# tally-controller-shield-smd.net
KiCad netlist of a schematic drawn in EAGLE
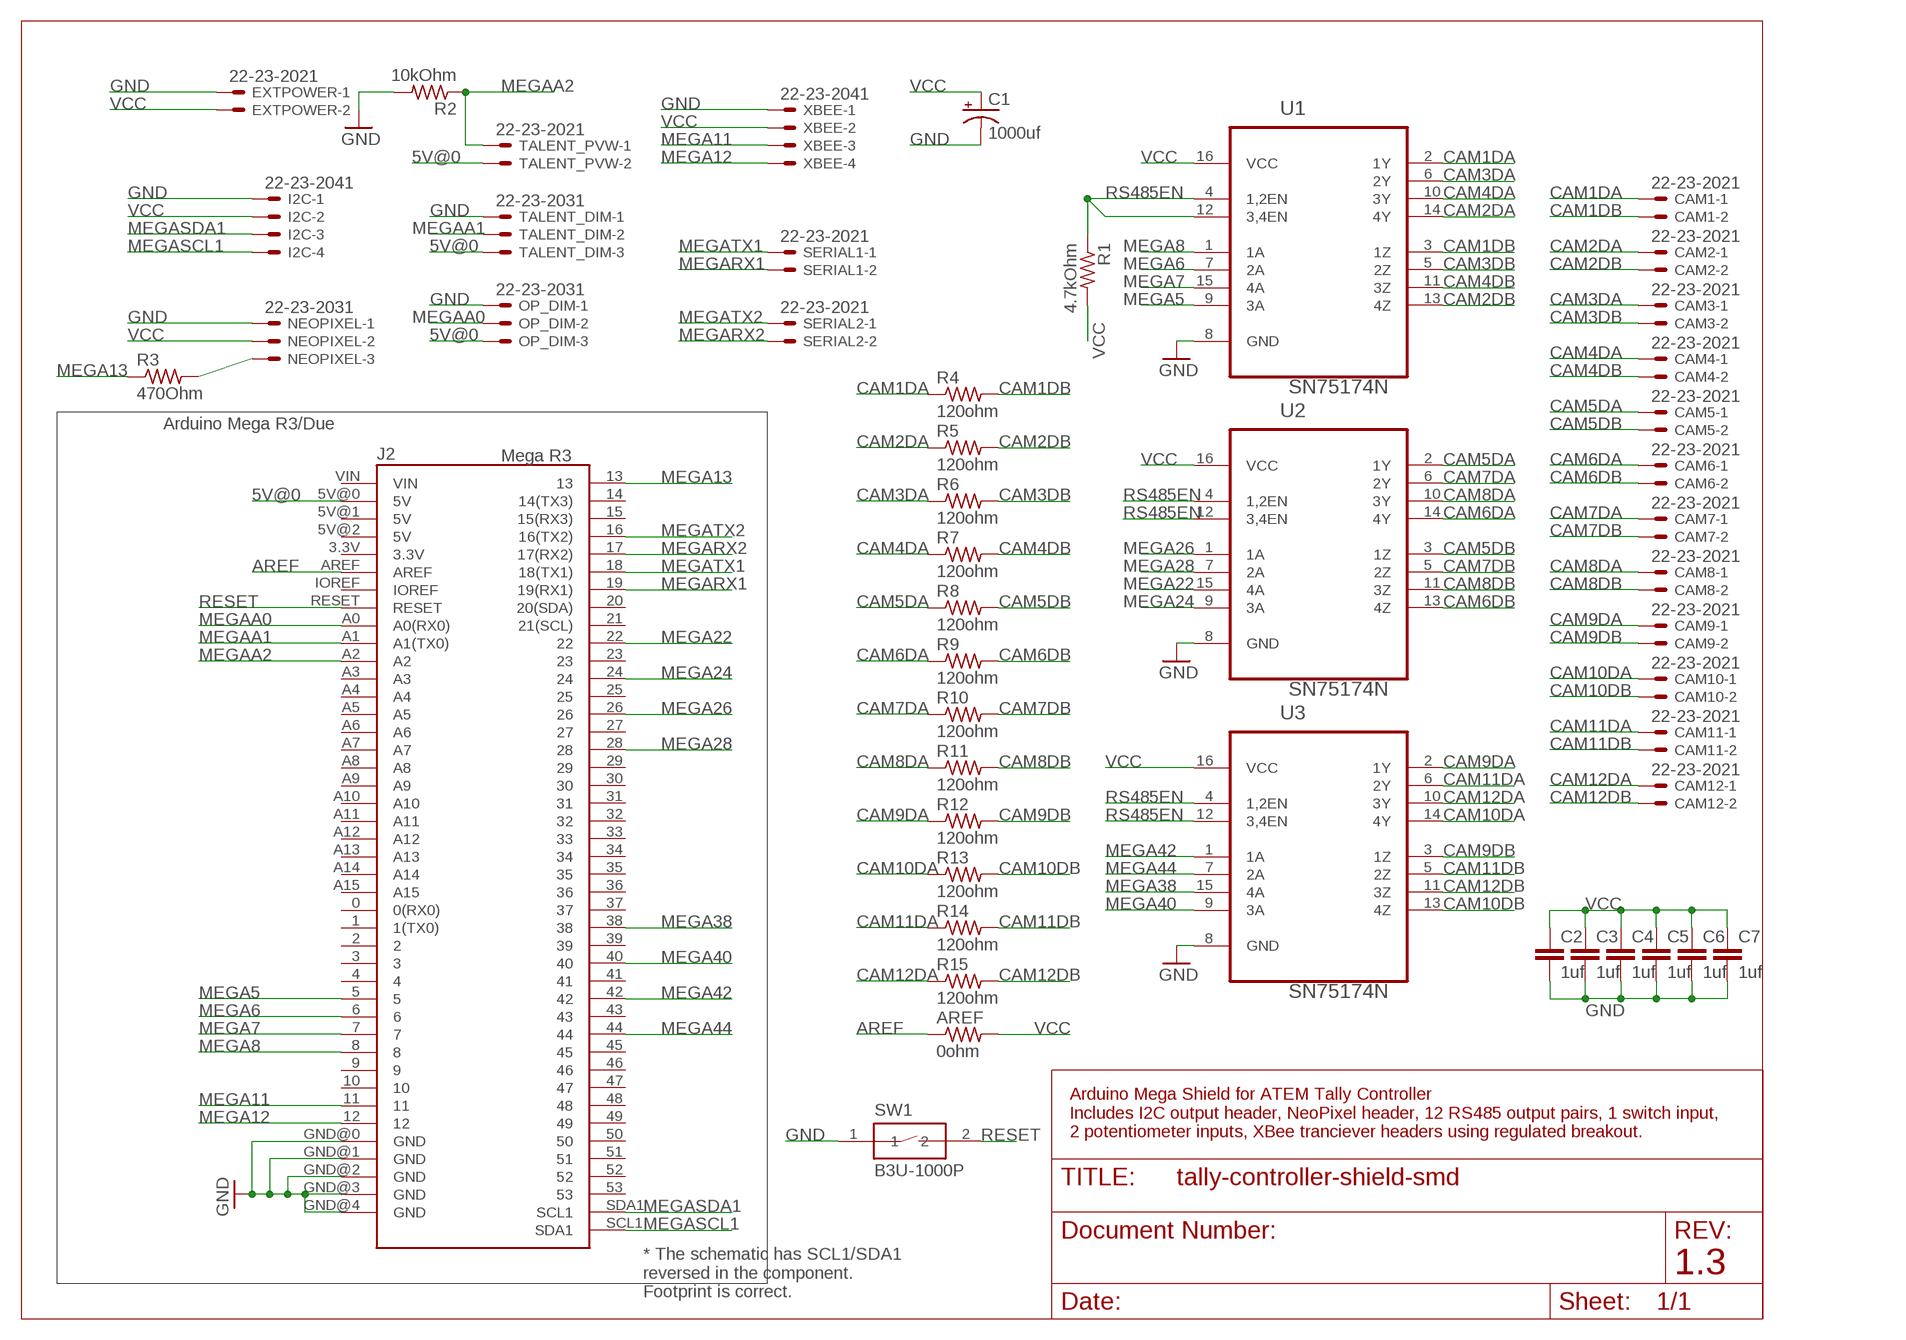
[diagram p0: schematic, sheet 1]

(export (version "E")
  (design (tool "Eeschema 10.0.6"))
  (components
    (comp (ref "AREF")
      (value "0ohm")
      (footprint "eagle-import:0204V")
      (libsource (lib "eagle-import") (part "R-US_0204/2V"))
    )
    (comp (ref "C1")
      (value "1000uf")
      (footprint "eagle-import:CPOL-RADIAL-5MM-10MM")
      (libsource (lib "eagle-import") (part "1000UF-RADIAL-5MM-25V-20%"))
    )
    (comp (ref "C2")
      (value "1uf")
      (footprint "eagle-import:RESC0805_N")
      (libsource (lib "eagle-import") (part "CAPACITOR_0805_N"))
    )
    (comp (ref "C3")
      (value "1uf")
      (footprint "eagle-import:RESC0805_N")
      (libsource (lib "eagle-import") (part "CAPACITOR_0805_N"))
    )
    (comp (ref "C4")
      (value "1uf")
      (footprint "eagle-import:RESC0805_N")
      (libsource (lib "eagle-import") (part "CAPACITOR_0805_N"))
    )
    (comp (ref "C5")
      (value "1uf")
      (footprint "eagle-import:RESC0805_N")
      (libsource (lib "eagle-import") (part "CAPACITOR_0805_N"))
    )
    (comp (ref "C6")
      (value "1uf")
      (footprint "eagle-import:RESC0805_N")
      (libsource (lib "eagle-import") (part "CAPACITOR_0805_N"))
    )
    (comp (ref "C7")
      (value "1uf")
      (footprint "eagle-import:RESC0805_N")
      (libsource (lib "eagle-import") (part "CAPACITOR_0805_N"))
    )
    (comp (ref "CAM1")
      (value "22-23-2021")
      (footprint "eagle-import:22-23-2021")
      (fields (field (name "MF") "MOLEX"))
      (libsource (lib "eagle-import") (part "22-23-2021"))
    )
    (comp (ref "CAM2")
      (value "22-23-2021")
      (footprint "eagle-import:22-23-2021")
      (fields (field (name "MF") "MOLEX"))
      (libsource (lib "eagle-import") (part "22-23-2021"))
    )
    (comp (ref "CAM3")
      (value "22-23-2021")
      (footprint "eagle-import:22-23-2021")
      (fields (field (name "MF") "MOLEX"))
      (libsource (lib "eagle-import") (part "22-23-2021"))
    )
    (comp (ref "CAM4")
      (value "22-23-2021")
      (footprint "eagle-import:22-23-2021")
      (fields (field (name "MF") "MOLEX"))
      (libsource (lib "eagle-import") (part "22-23-2021"))
    )
    (comp (ref "CAM5")
      (value "22-23-2021")
      (footprint "eagle-import:22-23-2021")
      (fields (field (name "MF") "MOLEX"))
      (libsource (lib "eagle-import") (part "22-23-2021"))
    )
    (comp (ref "CAM6")
      (value "22-23-2021")
      (footprint "eagle-import:22-23-2021")
      (fields (field (name "MF") "MOLEX"))
      (libsource (lib "eagle-import") (part "22-23-2021"))
    )
    (comp (ref "CAM7")
      (value "22-23-2021")
      (footprint "eagle-import:22-23-2021")
      (fields (field (name "MF") "MOLEX"))
      (libsource (lib "eagle-import") (part "22-23-2021"))
    )
    (comp (ref "CAM8")
      (value "22-23-2021")
      (footprint "eagle-import:22-23-2021")
      (fields (field (name "MF") "MOLEX"))
      (libsource (lib "eagle-import") (part "22-23-2021"))
    )
    (comp (ref "CAM9")
      (value "22-23-2021")
      (footprint "eagle-import:22-23-2021")
      (fields (field (name "MF") "MOLEX"))
      (libsource (lib "eagle-import") (part "22-23-2021"))
    )
    (comp (ref "CAM10")
      (value "22-23-2021")
      (footprint "eagle-import:22-23-2021")
      (fields (field (name "MF") "MOLEX"))
      (libsource (lib "eagle-import") (part "22-23-2021"))
    )
    (comp (ref "CAM11")
      (value "22-23-2021")
      (footprint "eagle-import:22-23-2021")
      (fields (field (name "MF") "MOLEX"))
      (libsource (lib "eagle-import") (part "22-23-2021"))
    )
    (comp (ref "CAM12")
      (value "22-23-2021")
      (footprint "eagle-import:22-23-2021")
      (fields (field (name "MF") "MOLEX"))
      (libsource (lib "eagle-import") (part "22-23-2021"))
    )
    (comp (ref "EXTPOWER")
      (value "22-23-2021")
      (footprint "eagle-import:22-23-2021")
      (fields (field (name "MF") "MOLEX"))
      (libsource (lib "eagle-import") (part "22-23-2021"))
    )
    (comp (ref "I2C")
      (value "22-23-2041")
      (footprint "eagle-import:22-23-2041")
      (fields (field (name "MF") "MOLEX"))
      (libsource (lib "eagle-import") (part "22-23-2041"))
    )
    (comp (ref "J2")
      (value "Mega R3")
      (footprint "eagle-import:ARDUINO_MEGA")
      (libsource (lib "eagle-import") (part "ARDUINO-MEGAFULL"))
    )
    (comp (ref "NEOPIXEL")
      (value "22-23-2031")
      (footprint "eagle-import:22-23-2031")
      (fields (field (name "MF") "MOLEX"))
      (libsource (lib "eagle-import") (part "22-23-2031"))
    )
    (comp (ref "OP_DIM")
      (value "22-23-2031")
      (footprint "eagle-import:22-23-2031")
      (fields (field (name "MF") "MOLEX"))
      (libsource (lib "eagle-import") (part "22-23-2031"))
    )
    (comp (ref "R1")
      (value "4.7kOhm")
      (footprint "eagle-import:R0805")
      (libsource (lib "eagle-import") (part "rcl_334_R-US_R0805"))
    )
    (comp (ref "R2")
      (value "10kOhm")
      (footprint "eagle-import:R0805")
      (libsource (lib "eagle-import") (part "rcl_334_R-US_R0805"))
    )
    (comp (ref "R3")
      (value "470Ohm")
      (footprint "eagle-import:R0805")
      (libsource (lib "eagle-import") (part "rcl_334_R-US_R0805"))
    )
    (comp (ref "R4")
      (value "120ohm")
      (footprint "eagle-import:R0805")
      (libsource (lib "eagle-import") (part "rcl_334_R-US_R0805"))
    )
    (comp (ref "R5")
      (value "120ohm")
      (footprint "eagle-import:R0805")
      (libsource (lib "eagle-import") (part "rcl_334_R-US_R0805"))
    )
    (comp (ref "R6")
      (value "120ohm")
      (footprint "eagle-import:R0805")
      (libsource (lib "eagle-import") (part "rcl_334_R-US_R0805"))
    )
    (comp (ref "R7")
      (value "120ohm")
      (footprint "eagle-import:R0805")
      (libsource (lib "eagle-import") (part "rcl_334_R-US_R0805"))
    )
    (comp (ref "R8")
      (value "120ohm")
      (footprint "eagle-import:R0805")
      (libsource (lib "eagle-import") (part "rcl_334_R-US_R0805"))
    )
    (comp (ref "R9")
      (value "120ohm")
      (footprint "eagle-import:R0805")
      (libsource (lib "eagle-import") (part "rcl_334_R-US_R0805"))
    )
    (comp (ref "R10")
      (value "120ohm")
      (footprint "eagle-import:R0805")
      (libsource (lib "eagle-import") (part "rcl_334_R-US_R0805"))
    )
    (comp (ref "R11")
      (value "120ohm")
      (footprint "eagle-import:R0805")
      (libsource (lib "eagle-import") (part "rcl_334_R-US_R0805"))
    )
    (comp (ref "R12")
      (value "120ohm")
      (footprint "eagle-import:R0805")
      (libsource (lib "eagle-import") (part "rcl_334_R-US_R0805"))
    )
    (comp (ref "R13")
      (value "120ohm")
      (footprint "eagle-import:R0805")
      (libsource (lib "eagle-import") (part "rcl_334_R-US_R0805"))
    )
    (comp (ref "R14")
      (value "120ohm")
      (footprint "eagle-import:R0805")
      (libsource (lib "eagle-import") (part "rcl_334_R-US_R0805"))
    )
    (comp (ref "R15")
      (value "120ohm")
      (footprint "eagle-import:R0805")
      (libsource (lib "eagle-import") (part "rcl_334_R-US_R0805"))
    )
    (comp (ref "SERIAL1")
      (value "22-23-2021")
      (footprint "eagle-import:22-23-2021")
      (fields (field (name "MF") "MOLEX"))
      (libsource (lib "eagle-import") (part "22-23-2021"))
    )
    (comp (ref "SERIAL2")
      (value "22-23-2021")
      (footprint "eagle-import:22-23-2021")
      (fields (field (name "MF") "MOLEX"))
      (libsource (lib "eagle-import") (part "22-23-2021"))
    )
    (comp (ref "SW1")
      (value "B3U-1000P")
      (footprint "eagle-import:B3U-1000P")
      (fields
        (field (name "DIGI_KEY_PART_NUMBER") "SW1020CT-ND")
        (field (name "MANUFACTURER") "Omron Electronics Inc-EMC Div")
        (field (name "CREATED_BY") "PCBLayout.com")
      )
      (libsource (lib "eagle-import") (part "B3U-1000P"))
    )
    (comp (ref "TALENT_DIM")
      (value "22-23-2031")
      (footprint "eagle-import:22-23-2031")
      (fields (field (name "MF") "MOLEX"))
      (libsource (lib "eagle-import") (part "22-23-2031"))
    )
    (comp (ref "TALENT_PVW")
      (value "22-23-2021")
      (footprint "eagle-import:22-23-2021")
      (fields (field (name "MF") "MOLEX"))
      (libsource (lib "eagle-import") (part "22-23-2021"))
    )
    (comp (ref "U1")
      (value "SN75174N")
      (footprint "eagle-import:DIP254P762X508-16")
      (fields (field (name "MF") "Texas Instruments"))
      (libsource (lib "eagle-import") (part "SN75174N"))
    )
    (comp (ref "U2")
      (value "SN75174N")
      (footprint "eagle-import:DIP254P762X508-16")
      (fields (field (name "MF") "Texas Instruments"))
      (libsource (lib "eagle-import") (part "SN75174N"))
    )
    (comp (ref "U3")
      (value "SN75174N")
      (footprint "eagle-import:DIP254P762X508-16")
      (fields (field (name "MF") "Texas Instruments"))
      (libsource (lib "eagle-import") (part "SN75174N"))
    )
    (comp (ref "XBEE")
      (value "22-23-2041")
      (footprint "eagle-import:22-23-2041")
      (fields (field (name "MF") "MOLEX"))
      (libsource (lib "eagle-import") (part "22-23-2041"))
    )
  )
  (nets
    (net (code "1") (name "/5V@0") (class "Default")
      (node (ref "J2") (pin "5V@0") (pinfunction "5V_5V@0") (pintype "bidirectional"))
      (node (ref "OP_DIM") (pin "3") (pinfunction "S_3") (pintype "passive"))
      (node (ref "TALENT_DIM") (pin "3") (pinfunction "S_3") (pintype "passive"))
      (node (ref "TALENT_PVW") (pin "2") (pinfunction "S_2") (pintype "passive"))
    )
    (net (code "2") (name "/AREF") (class "Default")
      (node (ref "AREF") (pin "1") (pinfunction "1_1") (pintype "passive"))
      (node (ref "J2") (pin "AREF") (pinfunction "AREF_AREF") (pintype "bidirectional"))
    )
    (net (code "3") (name "/CAM1DA") (class "Default")
      (node (ref "CAM1") (pin "1") (pinfunction "S_1") (pintype "passive"))
      (node (ref "R4") (pin "1") (pinfunction "1_1") (pintype "passive"))
      (node (ref "U1") (pin "2") (pinfunction "1Y_2") (pintype "output"))
    )
    (net (code "4") (name "/CAM1DB") (class "Default")
      (node (ref "CAM1") (pin "2") (pinfunction "S_2") (pintype "passive"))
      (node (ref "R4") (pin "2") (pinfunction "2_2") (pintype "passive"))
      (node (ref "U1") (pin "3") (pinfunction "1Z_3") (pintype "output"))
    )
    (net (code "5") (name "/CAM2DA") (class "Default")
      (node (ref "CAM2") (pin "1") (pinfunction "S_1") (pintype "passive"))
      (node (ref "R5") (pin "1") (pinfunction "1_1") (pintype "passive"))
      (node (ref "U1") (pin "14") (pinfunction "4Y_14") (pintype "output"))
    )
    (net (code "6") (name "/CAM2DB") (class "Default")
      (node (ref "CAM2") (pin "2") (pinfunction "S_2") (pintype "passive"))
      (node (ref "R5") (pin "2") (pinfunction "2_2") (pintype "passive"))
      (node (ref "U1") (pin "13") (pinfunction "4Z_13") (pintype "output"))
    )
    (net (code "7") (name "/CAM3DA") (class "Default")
      (node (ref "CAM3") (pin "1") (pinfunction "S_1") (pintype "passive"))
      (node (ref "R6") (pin "1") (pinfunction "1_1") (pintype "passive"))
      (node (ref "U1") (pin "6") (pinfunction "2Y_6") (pintype "output"))
    )
    (net (code "8") (name "/CAM3DB") (class "Default")
      (node (ref "CAM3") (pin "2") (pinfunction "S_2") (pintype "passive"))
      (node (ref "R6") (pin "2") (pinfunction "2_2") (pintype "passive"))
      (node (ref "U1") (pin "5") (pinfunction "2Z_5") (pintype "output"))
    )
    (net (code "9") (name "/CAM4DA") (class "Default")
      (node (ref "CAM4") (pin "1") (pinfunction "S_1") (pintype "passive"))
      (node (ref "R7") (pin "1") (pinfunction "1_1") (pintype "passive"))
      (node (ref "U1") (pin "10") (pinfunction "3Y_10") (pintype "output"))
    )
    (net (code "10") (name "/CAM4DB") (class "Default")
      (node (ref "CAM4") (pin "2") (pinfunction "S_2") (pintype "passive"))
      (node (ref "R7") (pin "2") (pinfunction "2_2") (pintype "passive"))
      (node (ref "U1") (pin "11") (pinfunction "3Z_11") (pintype "output"))
    )
    (net (code "11") (name "/CAM5DA") (class "Default")
      (node (ref "CAM5") (pin "1") (pinfunction "S_1") (pintype "passive"))
      (node (ref "R8") (pin "1") (pinfunction "1_1") (pintype "passive"))
      (node (ref "U2") (pin "2") (pinfunction "1Y_2") (pintype "output"))
    )
    (net (code "12") (name "/CAM5DB") (class "Default")
      (node (ref "CAM5") (pin "2") (pinfunction "S_2") (pintype "passive"))
      (node (ref "R8") (pin "2") (pinfunction "2_2") (pintype "passive"))
      (node (ref "U2") (pin "3") (pinfunction "1Z_3") (pintype "output"))
    )
    (net (code "13") (name "/CAM6DA") (class "Default")
      (node (ref "CAM6") (pin "1") (pinfunction "S_1") (pintype "passive"))
      (node (ref "R9") (pin "1") (pinfunction "1_1") (pintype "passive"))
      (node (ref "U2") (pin "14") (pinfunction "4Y_14") (pintype "output"))
    )
    (net (code "14") (name "/CAM6DB") (class "Default")
      (node (ref "CAM6") (pin "2") (pinfunction "S_2") (pintype "passive"))
      (node (ref "R9") (pin "2") (pinfunction "2_2") (pintype "passive"))
      (node (ref "U2") (pin "13") (pinfunction "4Z_13") (pintype "output"))
    )
    (net (code "15") (name "/CAM7DA") (class "Default")
      (node (ref "CAM7") (pin "1") (pinfunction "S_1") (pintype "passive"))
      (node (ref "R10") (pin "1") (pinfunction "1_1") (pintype "passive"))
      (node (ref "U2") (pin "6") (pinfunction "2Y_6") (pintype "output"))
    )
    (net (code "16") (name "/CAM7DB") (class "Default")
      (node (ref "CAM7") (pin "2") (pinfunction "S_2") (pintype "passive"))
      (node (ref "R10") (pin "2") (pinfunction "2_2") (pintype "passive"))
      (node (ref "U2") (pin "5") (pinfunction "2Z_5") (pintype "output"))
    )
    (net (code "17") (name "/CAM8DA") (class "Default")
      (node (ref "CAM8") (pin "1") (pinfunction "S_1") (pintype "passive"))
      (node (ref "R11") (pin "1") (pinfunction "1_1") (pintype "passive"))
      (node (ref "U2") (pin "10") (pinfunction "3Y_10") (pintype "output"))
    )
    (net (code "18") (name "/CAM8DB") (class "Default")
      (node (ref "CAM8") (pin "2") (pinfunction "S_2") (pintype "passive"))
      (node (ref "R11") (pin "2") (pinfunction "2_2") (pintype "passive"))
      (node (ref "U2") (pin "11") (pinfunction "3Z_11") (pintype "output"))
    )
    (net (code "19") (name "/CAM9DA") (class "Default")
      (node (ref "CAM9") (pin "1") (pinfunction "S_1") (pintype "passive"))
      (node (ref "R12") (pin "1") (pinfunction "1_1") (pintype "passive"))
      (node (ref "U3") (pin "2") (pinfunction "1Y_2") (pintype "output"))
    )
    (net (code "20") (name "/CAM9DB") (class "Default")
      (node (ref "CAM9") (pin "2") (pinfunction "S_2") (pintype "passive"))
      (node (ref "R12") (pin "2") (pinfunction "2_2") (pintype "passive"))
      (node (ref "U3") (pin "3") (pinfunction "1Z_3") (pintype "output"))
    )
    (net (code "21") (name "/CAM10DA") (class "Default")
      (node (ref "CAM10") (pin "1") (pinfunction "S_1") (pintype "passive"))
      (node (ref "R13") (pin "1") (pinfunction "1_1") (pintype "passive"))
      (node (ref "U3") (pin "14") (pinfunction "4Y_14") (pintype "output"))
    )
    (net (code "22") (name "/CAM10DB") (class "Default")
      (node (ref "CAM10") (pin "2") (pinfunction "S_2") (pintype "passive"))
      (node (ref "R13") (pin "2") (pinfunction "2_2") (pintype "passive"))
      (node (ref "U3") (pin "13") (pinfunction "4Z_13") (pintype "output"))
    )
    (net (code "23") (name "/CAM11DA") (class "Default")
      (node (ref "CAM11") (pin "1") (pinfunction "S_1") (pintype "passive"))
      (node (ref "R14") (pin "1") (pinfunction "1_1") (pintype "passive"))
      (node (ref "U3") (pin "6") (pinfunction "2Y_6") (pintype "output"))
    )
    (net (code "24") (name "/CAM11DB") (class "Default")
      (node (ref "CAM11") (pin "2") (pinfunction "S_2") (pintype "passive"))
      (node (ref "R14") (pin "2") (pinfunction "2_2") (pintype "passive"))
      (node (ref "U3") (pin "5") (pinfunction "2Z_5") (pintype "output"))
    )
    (net (code "25") (name "/CAM12DA") (class "Default")
      (node (ref "CAM12") (pin "1") (pinfunction "S_1") (pintype "passive"))
      (node (ref "R15") (pin "1") (pinfunction "1_1") (pintype "passive"))
      (node (ref "U3") (pin "10") (pinfunction "3Y_10") (pintype "output"))
    )
    (net (code "26") (name "/CAM12DB") (class "Default")
      (node (ref "CAM12") (pin "2") (pinfunction "S_2") (pintype "passive"))
      (node (ref "R15") (pin "2") (pinfunction "2_2") (pintype "passive"))
      (node (ref "U3") (pin "11") (pinfunction "3Z_11") (pintype "output"))
    )
    (net (code "27") (name "/MEGA5") (class "Default")
      (node (ref "J2") (pin "5") (pinfunction "5_5") (pintype "bidirectional"))
      (node (ref "U1") (pin "9") (pinfunction "3A_9") (pintype "input"))
    )
    (net (code "28") (name "/MEGA6") (class "Default")
      (node (ref "J2") (pin "6") (pinfunction "6_6") (pintype "bidirectional"))
      (node (ref "U1") (pin "7") (pinfunction "2A_7") (pintype "input"))
    )
    (net (code "29") (name "/MEGA7") (class "Default")
      (node (ref "J2") (pin "7") (pinfunction "7_7") (pintype "bidirectional"))
      (node (ref "U1") (pin "15") (pinfunction "4A_15") (pintype "input"))
    )
    (net (code "30") (name "/MEGA8") (class "Default")
      (node (ref "J2") (pin "8") (pinfunction "8_8") (pintype "bidirectional"))
      (node (ref "U1") (pin "1") (pinfunction "1A_1") (pintype "input"))
    )
    (net (code "31") (name "/MEGA11") (class "Default")
      (node (ref "J2") (pin "11") (pinfunction "11_11") (pintype "bidirectional"))
      (node (ref "XBEE") (pin "3") (pinfunction "S_3") (pintype "passive"))
    )
    (net (code "32") (name "/MEGA12") (class "Default")
      (node (ref "J2") (pin "12") (pinfunction "12_12") (pintype "bidirectional"))
      (node (ref "XBEE") (pin "4") (pinfunction "S_4") (pintype "passive"))
    )
    (net (code "33") (name "/MEGA13") (class "Default")
      (node (ref "J2") (pin "13") (pinfunction "13_13") (pintype "bidirectional"))
      (node (ref "R3") (pin "1") (pinfunction "1_1") (pintype "passive"))
    )
    (net (code "34") (name "/MEGA22") (class "Default")
      (node (ref "J2") (pin "22") (pinfunction "22_22") (pintype "bidirectional"))
      (node (ref "U2") (pin "15") (pinfunction "4A_15") (pintype "input"))
    )
    (net (code "35") (name "/MEGA24") (class "Default")
      (node (ref "J2") (pin "24") (pinfunction "24_24") (pintype "bidirectional"))
      (node (ref "U2") (pin "9") (pinfunction "3A_9") (pintype "input"))
    )
    (net (code "36") (name "/MEGA26") (class "Default")
      (node (ref "J2") (pin "26") (pinfunction "26_26") (pintype "bidirectional"))
      (node (ref "U2") (pin "1") (pinfunction "1A_1") (pintype "input"))
    )
    (net (code "37") (name "/MEGA28") (class "Default")
      (node (ref "J2") (pin "28") (pinfunction "28_28") (pintype "bidirectional"))
      (node (ref "U2") (pin "7") (pinfunction "2A_7") (pintype "input"))
    )
    (net (code "38") (name "/MEGA38") (class "Default")
      (node (ref "J2") (pin "38") (pinfunction "38_38") (pintype "bidirectional"))
      (node (ref "U3") (pin "15") (pinfunction "4A_15") (pintype "input"))
    )
    (net (code "39") (name "/MEGA40") (class "Default")
      (node (ref "J2") (pin "40") (pinfunction "40_40") (pintype "bidirectional"))
      (node (ref "U3") (pin "9") (pinfunction "3A_9") (pintype "input"))
    )
    (net (code "40") (name "/MEGA42") (class "Default")
      (node (ref "J2") (pin "42") (pinfunction "42_42") (pintype "bidirectional"))
      (node (ref "U3") (pin "1") (pinfunction "1A_1") (pintype "input"))
    )
    (net (code "41") (name "/MEGA44") (class "Default")
      (node (ref "J2") (pin "44") (pinfunction "44_44") (pintype "bidirectional"))
      (node (ref "U3") (pin "7") (pinfunction "2A_7") (pintype "input"))
    )
    (net (code "42") (name "/MEGAA0") (class "Default")
      (node (ref "J2") (pin "A0") (pinfunction "A0(RX0)_A0") (pintype "bidirectional"))
      (node (ref "OP_DIM") (pin "2") (pinfunction "S_2") (pintype "passive"))
    )
    (net (code "43") (name "/MEGAA1") (class "Default")
      (node (ref "J2") (pin "A1") (pinfunction "A1(TX0)_A1") (pintype "bidirectional"))
      (node (ref "TALENT_DIM") (pin "2") (pinfunction "S_2") (pintype "passive"))
    )
    (net (code "44") (name "/MEGAA2") (class "Default")
      (node (ref "J2") (pin "A2") (pinfunction "A2_A2") (pintype "bidirectional"))
      (node (ref "R2") (pin "1") (pinfunction "1_1") (pintype "passive"))
      (node (ref "TALENT_PVW") (pin "1") (pinfunction "S_1") (pintype "passive"))
    )
    (net (code "45") (name "/MEGARX1") (class "Default")
      (node (ref "J2") (pin "19") (pinfunction "19(RX1)_19") (pintype "bidirectional"))
      (node (ref "SERIAL1") (pin "2") (pinfunction "S_2") (pintype "passive"))
    )
    (net (code "46") (name "/MEGARX2") (class "Default")
      (node (ref "J2") (pin "17") (pinfunction "17(RX2)_17") (pintype "bidirectional"))
      (node (ref "SERIAL2") (pin "2") (pinfunction "S_2") (pintype "passive"))
    )
    (net (code "47") (name "/MEGASCL1") (class "Default")
      (node (ref "I2C") (pin "4") (pinfunction "S_4") (pintype "passive"))
      (node (ref "J2") (pin "SCL1") (pinfunction "SDA1_SCL1") (pintype "bidirectional"))
    )
    (net (code "48") (name "/MEGASDA1") (class "Default")
      (node (ref "I2C") (pin "3") (pinfunction "S_3") (pintype "passive"))
      (node (ref "J2") (pin "SDA1") (pinfunction "SCL1_SDA1") (pintype "bidirectional"))
    )
    (net (code "49") (name "/MEGATX1") (class "Default")
      (node (ref "J2") (pin "18") (pinfunction "18(TX1)_18") (pintype "bidirectional"))
      (node (ref "SERIAL1") (pin "1") (pinfunction "S_1") (pintype "passive"))
    )
    (net (code "50") (name "/MEGATX2") (class "Default")
      (node (ref "J2") (pin "16") (pinfunction "16(TX2)_16") (pintype "bidirectional"))
      (node (ref "SERIAL2") (pin "1") (pinfunction "S_1") (pintype "passive"))
    )
    (net (code "51") (name "/RESET") (class "Default")
      (node (ref "J2") (pin "RESET") (pinfunction "RESET_RESET") (pintype "bidirectional"))
      (node (ref "SW1") (pin "2") (pinfunction "2_2") (pintype "passive"))
    )
    (net (code "52") (name "/RS485EN") (class "Default")
      (node (ref "R1") (pin "1") (pinfunction "1_1") (pintype "passive"))
      (node (ref "U1") (pin "12") (pinfunction "3,4EN_12") (pintype "input"))
      (node (ref "U1") (pin "4") (pinfunction "1,2EN_4") (pintype "input"))
      (node (ref "U2") (pin "12") (pinfunction "3,4EN_12") (pintype "input"))
      (node (ref "U2") (pin "4") (pinfunction "1,2EN_4") (pintype "input"))
      (node (ref "U3") (pin "12") (pinfunction "3,4EN_12") (pintype "input"))
      (node (ref "U3") (pin "4") (pinfunction "1,2EN_4") (pintype "input"))
    )
    (net (code "53") (name "/VCC") (class "Default")
      (node (ref "AREF") (pin "2") (pinfunction "2_2") (pintype "passive"))
      (node (ref "C1") (pin "+") (pinfunction "+_+") (pintype "passive"))
      (node (ref "C2") (pin "1") (pinfunction "1_1") (pintype "passive"))
      (node (ref "C3") (pin "1") (pinfunction "1_1") (pintype "passive"))
      (node (ref "C4") (pin "1") (pinfunction "1_1") (pintype "passive"))
      (node (ref "C5") (pin "1") (pinfunction "1_1") (pintype "passive"))
      (node (ref "C6") (pin "1") (pinfunction "1_1") (pintype "passive"))
      (node (ref "C7") (pin "1") (pinfunction "1_1") (pintype "passive"))
      (node (ref "EXTPOWER") (pin "2") (pinfunction "S_2") (pintype "passive"))
      (node (ref "I2C") (pin "2") (pinfunction "S_2") (pintype "passive"))
      (node (ref "NEOPIXEL") (pin "2") (pinfunction "S_2") (pintype "passive"))
      (node (ref "R1") (pin "2") (pinfunction "2_2") (pintype "passive"))
      (node (ref "U1") (pin "16") (pinfunction "VCC_16") (pintype "power_in"))
      (node (ref "U2") (pin "16") (pinfunction "VCC_16") (pintype "power_in"))
      (node (ref "U3") (pin "16") (pinfunction "VCC_16") (pintype "power_in"))
      (node (ref "XBEE") (pin "2") (pinfunction "S_2") (pintype "passive"))
    )
    (net (code "54") (name "GND") (class "Default")
      (node (ref "C1") (pin "-") (pinfunction "-_-") (pintype "passive"))
      (node (ref "C2") (pin "2") (pinfunction "2_2") (pintype "passive"))
      (node (ref "C3") (pin "2") (pinfunction "2_2") (pintype "passive"))
      (node (ref "C4") (pin "2") (pinfunction "2_2") (pintype "passive"))
      (node (ref "C5") (pin "2") (pinfunction "2_2") (pintype "passive"))
      (node (ref "C6") (pin "2") (pinfunction "2_2") (pintype "passive"))
      (node (ref "C7") (pin "2") (pinfunction "2_2") (pintype "passive"))
      (node (ref "EXTPOWER") (pin "1") (pinfunction "S_1") (pintype "passive"))
      (node (ref "I2C") (pin "1") (pinfunction "S_1") (pintype "passive"))
      (node (ref "J2") (pin "GND@0") (pinfunction "GND_GND@0") (pintype "bidirectional"))
      (node (ref "J2") (pin "GND@1") (pinfunction "GND_GND@1") (pintype "bidirectional"))
      (node (ref "J2") (pin "GND@2") (pinfunction "GND_GND@2") (pintype "bidirectional"))
      (node (ref "J2") (pin "GND@3") (pinfunction "GND_GND@3") (pintype "bidirectional"))
      (node (ref "J2") (pin "GND@4") (pinfunction "GND_GND@4") (pintype "bidirectional"))
      (node (ref "NEOPIXEL") (pin "1") (pinfunction "S_1") (pintype "passive"))
      (node (ref "OP_DIM") (pin "1") (pinfunction "S_1") (pintype "passive"))
      (node (ref "R2") (pin "2") (pinfunction "2_2") (pintype "passive"))
      (node (ref "SW1") (pin "1") (pinfunction "1_1") (pintype "passive"))
      (node (ref "TALENT_DIM") (pin "1") (pinfunction "S_1") (pintype "passive"))
      (node (ref "U1") (pin "8") (pinfunction "GND_8") (pintype "passive"))
      (node (ref "U2") (pin "8") (pinfunction "GND_8") (pintype "passive"))
      (node (ref "U3") (pin "8") (pinfunction "GND_8") (pintype "passive"))
      (node (ref "XBEE") (pin "1") (pinfunction "S_1") (pintype "passive"))
    )
    (net (code "55") (name "Net-(NEOPIXELC-S)") (class "Default")
      (node (ref "NEOPIXEL") (pin "3") (pinfunction "S_3") (pintype "passive"))
      (node (ref "R3") (pin "2") (pinfunction "2_2") (pintype "passive"))
    )
    (net (code "56") (name "unconnected-(J2-0(RX0)-Pad0)") (class "Default")
      (node (ref "J2") (pin "0") (pinfunction "0(RX0)_0") (pintype "bidirectional"))
    )
    (net (code "57") (name "unconnected-(J2-1(TX0)-Pad1)") (class "Default")
      (node (ref "J2") (pin "1") (pinfunction "1(TX0)_1") (pintype "bidirectional"))
    )
    (net (code "58") (name "unconnected-(J2-5V-Pad5V@1)") (class "Default")
      (node (ref "J2") (pin "5V@1") (pinfunction "5V_5V@1") (pintype "bidirectional"))
    )
    (net (code "59") (name "unconnected-(J2-5V-Pad5V@2)") (class "Default")
      (node (ref "J2") (pin "5V@2") (pinfunction "5V_5V@2") (pintype "bidirectional"))
    )
    (net (code "60") (name "unconnected-(J2-14(TX3)-Pad14)") (class "Default")
      (node (ref "J2") (pin "14") (pinfunction "14(TX3)_14") (pintype "bidirectional"))
    )
    (net (code "61") (name "unconnected-(J2-15(RX3)-Pad15)") (class "Default")
      (node (ref "J2") (pin "15") (pinfunction "15(RX3)_15") (pintype "bidirectional"))
    )
    (net (code "62") (name "unconnected-(J2-20(SDA)-Pad20)") (class "Default")
      (node (ref "J2") (pin "20") (pinfunction "20(SDA)_20") (pintype "bidirectional"))
    )
    (net (code "63") (name "unconnected-(J2-21(SCL)-Pad21)") (class "Default")
      (node (ref "J2") (pin "21") (pinfunction "21(SCL)_21") (pintype "bidirectional"))
    )
    (net (code "64") (name "unconnected-(J2-Pad2)") (class "Default")
      (node (ref "J2") (pin "2") (pinfunction "2_2") (pintype "bidirectional"))
    )
    (net (code "65") (name "unconnected-(J2-Pad3)") (class "Default")
      (node (ref "J2") (pin "3") (pinfunction "3_3") (pintype "bidirectional"))
    )
    (net (code "66") (name "unconnected-(J2-Pad3.3V)") (class "Default")
      (node (ref "J2") (pin "3.3V") (pinfunction "3.3V_3.3V") (pintype "bidirectional"))
    )
    (net (code "67") (name "unconnected-(J2-Pad4)") (class "Default")
      (node (ref "J2") (pin "4") (pinfunction "4_4") (pintype "bidirectional"))
    )
    (net (code "68") (name "unconnected-(J2-Pad9)") (class "Default")
      (node (ref "J2") (pin "9") (pinfunction "9_9") (pintype "bidirectional"))
    )
    (net (code "69") (name "unconnected-(J2-Pad10)") (class "Default")
      (node (ref "J2") (pin "10") (pinfunction "10_10") (pintype "bidirectional"))
    )
    (net (code "70") (name "unconnected-(J2-Pad23)") (class "Default")
      (node (ref "J2") (pin "23") (pinfunction "23_23") (pintype "bidirectional"))
    )
    (net (code "71") (name "unconnected-(J2-Pad25)") (class "Default")
      (node (ref "J2") (pin "25") (pinfunction "25_25") (pintype "bidirectional"))
    )
    (net (code "72") (name "unconnected-(J2-Pad27)") (class "Default")
      (node (ref "J2") (pin "27") (pinfunction "27_27") (pintype "bidirectional"))
    )
    (net (code "73") (name "unconnected-(J2-Pad29)") (class "Default")
      (node (ref "J2") (pin "29") (pinfunction "29_29") (pintype "bidirectional"))
    )
    (net (code "74") (name "unconnected-(J2-Pad30)") (class "Default")
      (node (ref "J2") (pin "30") (pinfunction "30_30") (pintype "bidirectional"))
    )
    (net (code "75") (name "unconnected-(J2-Pad31)") (class "Default")
      (node (ref "J2") (pin "31") (pinfunction "31_31") (pintype "bidirectional"))
    )
    (net (code "76") (name "unconnected-(J2-Pad32)") (class "Default")
      (node (ref "J2") (pin "32") (pinfunction "32_32") (pintype "bidirectional"))
    )
    (net (code "77") (name "unconnected-(J2-Pad33)") (class "Default")
      (node (ref "J2") (pin "33") (pinfunction "33_33") (pintype "bidirectional"))
    )
    (net (code "78") (name "unconnected-(J2-Pad34)") (class "Default")
      (node (ref "J2") (pin "34") (pinfunction "34_34") (pintype "bidirectional"))
    )
    (net (code "79") (name "unconnected-(J2-Pad35)") (class "Default")
      (node (ref "J2") (pin "35") (pinfunction "35_35") (pintype "bidirectional"))
    )
    (net (code "80") (name "unconnected-(J2-Pad36)") (class "Default")
      (node (ref "J2") (pin "36") (pinfunction "36_36") (pintype "bidirectional"))
    )
    (net (code "81") (name "unconnected-(J2-Pad37)") (class "Default")
      (node (ref "J2") (pin "37") (pinfunction "37_37") (pintype "bidirectional"))
    )
    (net (code "82") (name "unconnected-(J2-Pad39)") (class "Default")
      (node (ref "J2") (pin "39") (pinfunction "39_39") (pintype "bidirectional"))
    )
    (net (code "83") (name "unconnected-(J2-Pad41)") (class "Default")
      (node (ref "J2") (pin "41") (pinfunction "41_41") (pintype "bidirectional"))
    )
    (net (code "84") (name "unconnected-(J2-Pad43)") (class "Default")
      (node (ref "J2") (pin "43") (pinfunction "43_43") (pintype "bidirectional"))
    )
    (net (code "85") (name "unconnected-(J2-Pad45)") (class "Default")
      (node (ref "J2") (pin "45") (pinfunction "45_45") (pintype "bidirectional"))
    )
    (net (code "86") (name "unconnected-(J2-Pad46)") (class "Default")
      (node (ref "J2") (pin "46") (pinfunction "46_46") (pintype "bidirectional"))
    )
    (net (code "87") (name "unconnected-(J2-Pad47)") (class "Default")
      (node (ref "J2") (pin "47") (pinfunction "47_47") (pintype "bidirectional"))
    )
    (net (code "88") (name "unconnected-(J2-Pad48)") (class "Default")
      (node (ref "J2") (pin "48") (pinfunction "48_48") (pintype "bidirectional"))
    )
    (net (code "89") (name "unconnected-(J2-Pad49)") (class "Default")
      (node (ref "J2") (pin "49") (pinfunction "49_49") (pintype "bidirectional"))
    )
    (net (code "90") (name "unconnected-(J2-Pad50)") (class "Default")
      (node (ref "J2") (pin "50") (pinfunction "50_50") (pintype "bidirectional"))
    )
    (net (code "91") (name "unconnected-(J2-Pad51)") (class "Default")
      (node (ref "J2") (pin "51") (pinfunction "51_51") (pintype "bidirectional"))
    )
    (net (code "92") (name "unconnected-(J2-Pad52)") (class "Default")
      (node (ref "J2") (pin "52") (pinfunction "52_52") (pintype "bidirectional"))
    )
    (net (code "93") (name "unconnected-(J2-Pad53)") (class "Default")
      (node (ref "J2") (pin "53") (pinfunction "53_53") (pintype "bidirectional"))
    )
    (net (code "94") (name "unconnected-(J2-PadA3)") (class "Default")
      (node (ref "J2") (pin "A3") (pinfunction "A3_A3") (pintype "bidirectional"))
    )
    (net (code "95") (name "unconnected-(J2-PadA4)") (class "Default")
      (node (ref "J2") (pin "A4") (pinfunction "A4_A4") (pintype "bidirectional"))
    )
    (net (code "96") (name "unconnected-(J2-PadA5)") (class "Default")
      (node (ref "J2") (pin "A5") (pinfunction "A5_A5") (pintype "bidirectional"))
    )
    (net (code "97") (name "unconnected-(J2-PadA6)") (class "Default")
      (node (ref "J2") (pin "A6") (pinfunction "A6_A6") (pintype "bidirectional"))
    )
    (net (code "98") (name "unconnected-(J2-PadA7)") (class "Default")
      (node (ref "J2") (pin "A7") (pinfunction "A7_A7") (pintype "bidirectional"))
    )
    (net (code "99") (name "unconnected-(J2-PadA8)") (class "Default")
      (node (ref "J2") (pin "A8") (pinfunction "A8_A8") (pintype "bidirectional"))
    )
    (net (code "100") (name "unconnected-(J2-PadA9)") (class "Default")
      (node (ref "J2") (pin "A9") (pinfunction "A9_A9") (pintype "bidirectional"))
    )
    (net (code "101") (name "unconnected-(J2-PadA10)") (class "Default")
      (node (ref "J2") (pin "A10") (pinfunction "A10_A10") (pintype "bidirectional"))
    )
    (net (code "102") (name "unconnected-(J2-PadA11)") (class "Default")
      (node (ref "J2") (pin "A11") (pinfunction "A11_A11") (pintype "bidirectional"))
    )
    (net (code "103") (name "unconnected-(J2-PadA12)") (class "Default")
      (node (ref "J2") (pin "A12") (pinfunction "A12_A12") (pintype "bidirectional"))
    )
    (net (code "104") (name "unconnected-(J2-PadA13)") (class "Default")
      (node (ref "J2") (pin "A13") (pinfunction "A13_A13") (pintype "bidirectional"))
    )
    (net (code "105") (name "unconnected-(J2-PadA14)") (class "Default")
      (node (ref "J2") (pin "A14") (pinfunction "A14_A14") (pintype "bidirectional"))
    )
    (net (code "106") (name "unconnected-(J2-PadA15)") (class "Default")
      (node (ref "J2") (pin "A15") (pinfunction "A15_A15") (pintype "bidirectional"))
    )
    (net (code "107") (name "unconnected-(J2-PadIOREF)") (class "Default")
      (node (ref "J2") (pin "IOREF") (pinfunction "IOREF_IOREF") (pintype "bidirectional"))
    )
    (net (code "108") (name "unconnected-(J2-PadVIN)") (class "Default")
      (node (ref "J2") (pin "VIN") (pinfunction "VIN_VIN") (pintype "bidirectional"))
    )
  )
)
